# Power.net
KiCad netlist of a schematic drawn in Altium Designer
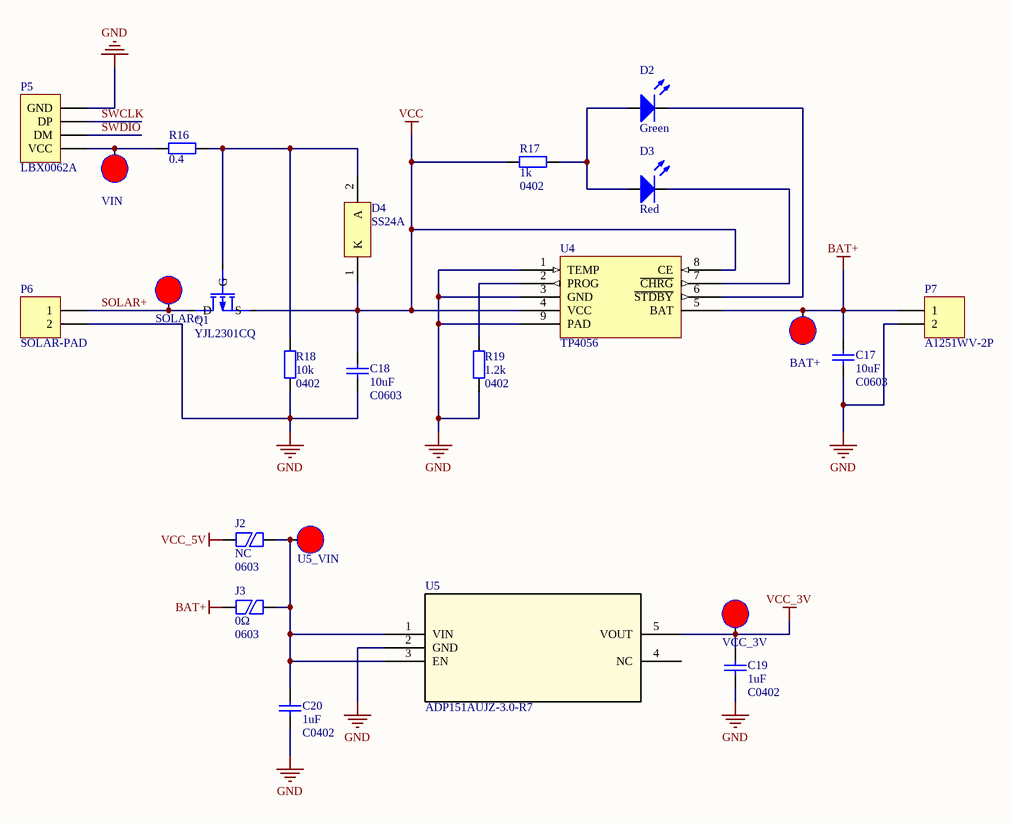
[diagram p0: Power.SchDoc]

(export (version "E")
  (design (tool "Eeschema 10.0.6"))
  (components
    (comp (ref "BAT+")
      (value "TP-EMB-SMT-Single-20mil-1pin")
      (footprint "EMB-SMT-40MILX40MIL")
      (description "Test Point Designed for holding a standard probe lead")
      (libsource (lib "RFID_CC1101_433MHz") (part "TP-EMB-SMT-Single-20mil-1pin"))
    )
    (comp (ref "C17")
      (value "10uF")
      (footprint "1608[0603]")
      (description "Capacitor(0603,X5R(EIA),10uF,DC 25V,+/-20 %) muRata")
      (fields (field (name "PACKAGEREFERENCE") "C0603") (field (name "PUBLISHER") "Altium Limited"))
      (libsource (lib "RFID_CC1101_433MHz") (part "GRM188R61E106MA73"))
    )
    (comp (ref "C18")
      (value "10uF")
      (footprint "1608[0603]")
      (description "Capacitor(0603,X5R(EIA),10uF,DC 25V,+/-20 %) muRata")
      (fields (field (name "PACKAGEREFERENCE") "C0603") (field (name "PUBLISHER") "Altium Limited"))
      (libsource (lib "RFID_CC1101_433MHz") (part "GRM188R61E106MA73"))
    )
    (comp (ref "C19")
      (value "1uF")
      (footprint "0402")
      (description "Capacitor (0402,X5R,1uF,DC 25V,±10%) Murata")
      (fields (field (name "PACKAGEREFERENCE") "C0402") (field (name "PUBLISHER") "Altium Limited"))
      (libsource (lib "RFID_CC1101_433MHz") (part "GRM155R61E105KE11"))
    )
    (comp (ref "C20")
      (value "1uF")
      (footprint "0402")
      (description "Capacitor (0402,X5R,1uF,DC 25V,±10%) Murata")
      (fields (field (name "PACKAGEREFERENCE") "C0402") (field (name "PUBLISHER") "Altium Limited"))
      (libsource (lib "RFID_CC1101_433MHz") (part "GRM155R61E105KE11"))
    )
    (comp (ref "D2")
      (value "Green")
      (footprint "0603/K")
      (description "Standard 0603 SMD LED, Green, 1.6-2.2V")
      (fields (field (name "PUBLISHER") "Altium Limited"))
      (libsource (lib "RFID_CC1101_433MHz") (part "XL-1608SYGC"))
    )
    (comp (ref "D3")
      (value "Red")
      (footprint "0603/K")
      (description "Standard 0603 SMD LED, Red, 1.6-2.2V")
      (fields (field (name "PUBLISHER") "Altium Limited"))
      (libsource (lib "RFID_CC1101_433MHz") (part "XL-1608SURC"))
    )
    (comp (ref "D4")
      (value "SS24A")
      (footprint "ONSC-SMA-2-403D-02_V")
      (description "Surface Mount Schottky Rectifier, 2-Pin SMA, VRRM=40V , VF=0.5V at IF=2.0A, -55~+125°C")
      (fields (field (name "MANUFACTURER") "扬州扬杰电子科技股份有限公司"))
      (libsource (lib "RFID_CC1101_433MHz") (part "SS24A"))
    )
    (comp (ref "J2")
      (value "NC")
      (footprint "1608[0603] - jumper")
      (description "Resistor 0603(1608) 0Ω jumper")
      (fields (field (name "PACKAGEREFERENCE") "0603"))
      (libsource (lib "RFID_CC1101_433MHz") (part "RC0603JR-JUMP"))
    )
    (comp (ref "J3")
      (value "0Ω")
      (footprint "1608[0603] - jumper")
      (description "Resistor 0603(1608) 0Ω jumper")
      (fields (field (name "PACKAGEREFERENCE") "0603"))
      (libsource (lib "RFID_CC1101_433MHz") (part "RC0603JR-JUMP"))
    )
    (comp (ref "P5")
      (value "LBX0062A")
      (footprint "LBX0062A")
      (description "PogoPinLBX0062A, 4-Pin")
      (fields (field (name "PUBLISHER") "Altium Limited"))
      (libsource (lib "RFID_CC1101_433MHz") (part "LBX0062A"))
    )
    (comp (ref "P6")
      (value "SOLAR-PAD")
      (footprint "SOLAR-PAD")
      (description "Header, 2-Pin")
      (fields (field (name "PUBLISHER") "Altium Limited"))
      (libsource (lib "RFID_CC1101_433MHz") (part "SOLAR-PAD"))
    )
    (comp (ref "P7")
      (value "A1251WV-2P")
      (footprint "A1251WV-2P")
      (description "Header, 2-Pin, 1.25mm PITCH, 180° WAFER")
      (fields (field (name "PUBLISHER") "Altium Limited"))
      (libsource (lib "RFID_CC1101_433MHz") (part "A1251WV-2P"))
    )
    (comp (ref "Q1")
      (value "YJL2301CQ")
      (footprint "SOT95P237X112-3N")
      (fields (field (name "PUBLISHER") "Altium Limited"))
      (libsource (lib "RFID_CC1101_433MHz") (part "YJL2301CQ"))
    )
    (comp (ref "R16")
      (value "0.4")
      (footprint "RESC3216X07N")
      (description "Resistor 1206(3216) 0.4Ω ±1% 1W AUTOMOTIVE GRADEPE_L series")
      (libsource (lib "RFID_CC1101PA2") (part "PE1206FRF470R4L"))
    )
    (comp (ref "R17")
      (value "1k")
      (footprint "RESC1005X04N")
      (description "Resistor 0402(1005) 1kΩ ±1%")
      (fields (field (name "PACKAGEREFERENCE") "0402"))
      (libsource (lib "RFID_CC1101PA2") (part "RC0402FR-071KL"))
    )
    (comp (ref "R18")
      (value "10k")
      (footprint "RESC1005X04N")
      (description "Resistor 0402(1005) 10kΩ ±1%")
      (fields (field (name "PACKAGEREFERENCE") "0402"))
      (libsource (lib "RFID_CC1101PA2") (part "RC0402FR-0710KL"))
    )
    (comp (ref "R19")
      (value "1.2k")
      (footprint "RESC1005X04N")
      (description "Resistor 0402(1005) 1.2kΩ ±1%")
      (fields (field (name "PACKAGEREFERENCE") "0402"))
      (libsource (lib "RFID_CC1101PA2") (part "RC0402FR-071K2L"))
    )
    (comp (ref "SOLAR+")
      (value "TP-EMB-SMT-Single-20mil-1pin")
      (footprint "EMB-SMT-40MILX40MIL")
      (description "Test Point Designed for holding a standard probe lead")
      (libsource (lib "RFID_CC1101_433MHz") (part "TP-EMB-SMT-Single-20mil-1pin"))
    )
    (comp (ref "U4")
      (value "TP4056")
      (footprint "ESOP-9N")
      (description "1A线性锂离子电池充电器")
      (libsource (lib "BC26_GNSS") (part "TP4056"))
    )
    (comp (ref "U5")
      (value "ADP151AUJZ-3.0-R7")
      (footprint "UJ_5")
      (libsource (lib "RFID_CC1101_433MHz") (part "ADP151"))
    )
    (comp (ref "U5_VIN")
      (value "TP-EMB-SMT-Single-20mil-1pin")
      (footprint "EMB-SMT-40MILX40MIL")
      (description "Test Point Designed for holding a standard probe lead")
      (libsource (lib "RFID_CC1101_433MHz") (part "TP-EMB-SMT-Single-20mil-1pin"))
    )
    (comp (ref "VCC_3V")
      (value "TP-EMB-SMT-Single-20mil-1pin")
      (footprint "EMB-SMT-40MILX40MIL")
      (description "Test Point Designed for holding a standard probe lead")
      (libsource (lib "RFID_CC1101_433MHz") (part "TP-EMB-SMT-Single-20mil-1pin"))
    )
    (comp (ref "VIN")
      (value "TP-EMB-SMT-Single-20mil-1pin")
      (footprint "EMB-SMT-40MILX40MIL")
      (description "Test Point Designed for holding a standard probe lead")
      (libsource (lib "RFID_CC1101_433MHz") (part "TP-EMB-SMT-Single-20mil-1pin"))
    )
  )
  (nets
    (net (code "1") (name "/SOLAR+") (class "Default")
      (node (ref "P6") (pin "1") (pinfunction "1_1") (pintype "passive"))
      (node (ref "Q1") (pin "3") (pinfunction "D_3") (pintype "passive"))
      (node (ref "SOLAR+") (pin "1") (pinfunction "1_1") (pintype "passive"))
    )
    (net (code "2") (name "/SWCLK") (class "Default")
      (node (ref "P5") (pin "3") (pinfunction "DP_3") (pintype "passive"))
    )
    (net (code "3") (name "/SWDIO") (class "Default")
      (node (ref "P5") (pin "2") (pinfunction "DM_2") (pintype "passive"))
    )
    (net (code "4") (name "BAT+") (class "Default")
      (node (ref "BAT+") (pin "1") (pinfunction "1_1") (pintype "passive"))
      (node (ref "C17") (pin "2") (pinfunction "2_2") (pintype "passive"))
      (node (ref "J3") (pin "1") (pinfunction "1_1") (pintype "passive"))
      (node (ref "P7") (pin "1") (pinfunction "1_1") (pintype "passive"))
      (node (ref "U4") (pin "5") (pinfunction "BAT_5") (pintype "power_in"))
    )
    (net (code "5") (name "GND") (class "Default")
      (node (ref "C17") (pin "1") (pinfunction "1_1") (pintype "passive"))
      (node (ref "C18") (pin "2") (pinfunction "2_2") (pintype "passive"))
      (node (ref "C19") (pin "1") (pinfunction "1_1") (pintype "passive"))
      (node (ref "C20") (pin "1") (pinfunction "1_1") (pintype "passive"))
      (node (ref "P5") (pin "4") (pinfunction "GND_4") (pintype "passive"))
      (node (ref "P6") (pin "2") (pinfunction "2_2") (pintype "passive"))
      (node (ref "P7") (pin "2") (pinfunction "2_2") (pintype "passive"))
      (node (ref "R18") (pin "1") (pinfunction "1_1") (pintype "passive"))
      (node (ref "R19") (pin "1") (pinfunction "1_1") (pintype "passive"))
      (node (ref "U4") (pin "1") (pinfunction "TEMP_1") (pintype "input"))
      (node (ref "U4") (pin "3") (pinfunction "GND_3") (pintype "power_in"))
      (node (ref "U4") (pin "9") (pinfunction "PAD_9") (pintype "passive"))
      (node (ref "U5") (pin "2") (pinfunction "GND_2") (pintype "passive"))
    )
    (net (code "6") (name "Net-(D2-PadA)") (class "Default")
      (node (ref "D2") (pin "A") (pinfunction "A_A") (pintype "passive"))
      (node (ref "D3") (pin "A") (pinfunction "A_A") (pintype "passive"))
      (node (ref "R17") (pin "2") (pinfunction "2_2") (pintype "passive"))
    )
    (net (code "7") (name "Net-(D4-A)") (class "Default")
      (node (ref "D4") (pin "2") (pinfunction "A_2") (pintype "passive"))
      (node (ref "Q1") (pin "1") (pinfunction "G_1") (pintype "passive"))
      (node (ref "R16") (pin "2") (pinfunction "2_2") (pintype "passive"))
      (node (ref "R18") (pin "2") (pinfunction "2_2") (pintype "passive"))
    )
    (net (code "8") (name "Net-(P5-VCC)") (class "Default")
      (node (ref "P5") (pin "1") (pinfunction "VCC_1") (pintype "passive"))
      (node (ref "R16") (pin "1") (pinfunction "1_1") (pintype "passive"))
      (node (ref "VIN") (pin "1") (pinfunction "1_1") (pintype "passive"))
    )
    (net (code "9") (name "Net-(U4-PROG)") (class "Default")
      (node (ref "R19") (pin "2") (pinfunction "2_2") (pintype "passive"))
      (node (ref "U4") (pin "2") (pinfunction "PROG_2") (pintype "output"))
    )
    (net (code "10") (name "Net-(U4-~{CHRG})") (class "Default")
      (node (ref "D3") (pin "K") (pinfunction "K_K") (pintype "passive"))
      (node (ref "U4") (pin "7") (pinfunction "~{CHRG}_7") (pintype "output"))
    )
    (net (code "11") (name "Net-(U4-~{STDBY})") (class "Default")
      (node (ref "D2") (pin "K") (pinfunction "K_K") (pintype "passive"))
      (node (ref "U4") (pin "6") (pinfunction "~{STDBY}_6") (pintype "output"))
    )
    (net (code "12") (name "Net-(U5-EN)") (class "Default")
      (node (ref "C20") (pin "2") (pinfunction "2_2") (pintype "passive"))
      (node (ref "J2") (pin "2") (pinfunction "2_2") (pintype "passive"))
      (node (ref "J3") (pin "2") (pinfunction "2_2") (pintype "passive"))
      (node (ref "U5") (pin "1") (pinfunction "VIN_1") (pintype "passive"))
      (node (ref "U5") (pin "3") (pinfunction "EN_3") (pintype "passive"))
      (node (ref "U5_VIN") (pin "1") (pinfunction "1_1") (pintype "passive"))
    )
    (net (code "13") (name "VCC") (class "Default")
      (node (ref "C18") (pin "1") (pinfunction "1_1") (pintype "passive"))
      (node (ref "D4") (pin "1") (pinfunction "K_1") (pintype "passive"))
      (node (ref "Q1") (pin "2") (pinfunction "S_2") (pintype "passive"))
      (node (ref "R17") (pin "1") (pinfunction "1_1") (pintype "passive"))
      (node (ref "U4") (pin "4") (pinfunction "VCC_4") (pintype "power_in"))
      (node (ref "U4") (pin "8") (pinfunction "CE_8") (pintype "input"))
    )
    (net (code "14") (name "VCC_3V") (class "Default")
      (node (ref "C19") (pin "2") (pinfunction "2_2") (pintype "passive"))
      (node (ref "U5") (pin "5") (pinfunction "VOUT_5") (pintype "passive"))
      (node (ref "VCC_3V") (pin "1") (pinfunction "1_1") (pintype "passive"))
    )
    (net (code "15") (name "VCC_5V") (class "Default")
      (node (ref "J2") (pin "1") (pinfunction "1_1") (pintype "passive"))
    )
    (net (code "16") (name "unconnected-(U5-NC-Pad4)") (class "Default")
      (node (ref "U5") (pin "4") (pinfunction "NC_4") (pintype "passive"))
    )
  )
)
